# CW308T_ADUCM3029_UFO.net
KiCad netlist of a schematic drawn in Altium Designer
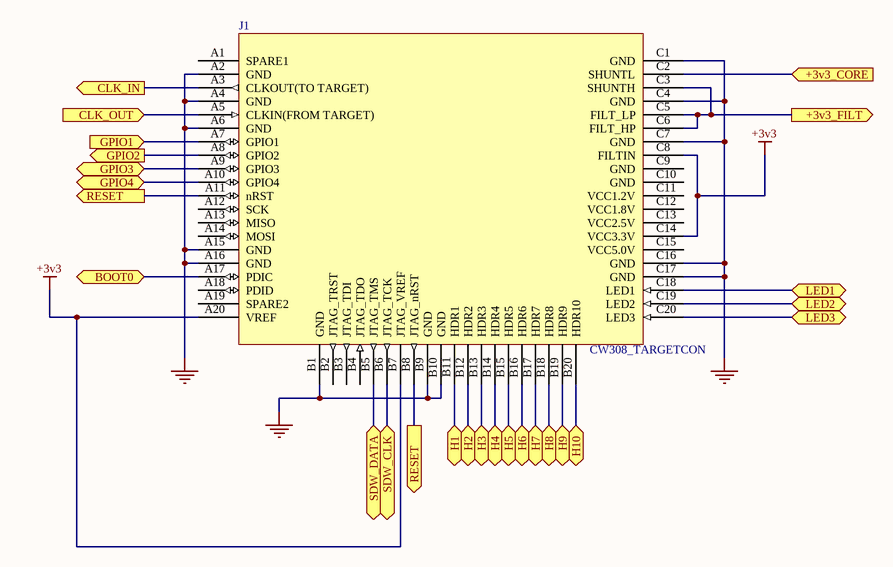
[diagram p0: CW308T_ADUCM3029_UFO.SchDoc]

(export (version "E")
  (design (tool "Eeschema 10.0.6"))
  (components
    (comp (ref "J1")
      (value "CW308_TARGETCON")
      (footprint "CW308_TBOARD_CONN")
      (description "CW308 \"Standard\" Target Board Connector")
      (fields (field (name "PART NUMBER") "CW308_TBOARD"))
      (libsource (lib "NewAE_AltiumLib") (part "CW308_TBOARD"))
    )
  )
  (nets
    (net (code "1") (name "+3v3") (class "Default")
      (node (ref "J1") (pin "A20") (pinfunction "VREF_A20") (pintype "tri_state"))
      (node (ref "J1") (pin "B7") (pinfunction "JTAG_VREF_B7") (pintype "tri_state"))
      (node (ref "J1") (pin "C14") (pinfunction "VCC3.3V_C14") (pintype "power_in"))
      (node (ref "J1") (pin "C8") (pinfunction "FILTIN_C8") (pintype "passive"))
    )
    (net (code "2") (name "/+3v3_CORE") (class "Default")
      (node (ref "J1") (pin "C2") (pinfunction "SHUNTL_C2") (pintype "passive"))
    )
    (net (code "3") (name "/+3v3_FILT") (class "Default")
      (node (ref "J1") (pin "C3") (pinfunction "SHUNTH_C3") (pintype "passive"))
      (node (ref "J1") (pin "C5") (pinfunction "FILT_LP_C5") (pintype "passive"))
      (node (ref "J1") (pin "C6") (pinfunction "FILT_HP_C6") (pintype "passive"))
    )
    (net (code "4") (name "/BOOT0") (class "Default")
      (node (ref "J1") (pin "A17") (pinfunction "PDIC_A17") (pintype "bidirectional"))
    )
    (net (code "5") (name "/CLK_IN") (class "Default")
      (node (ref "J1") (pin "A3") (pinfunction "CLKOUT(TO_TARGET)_A3") (pintype "output"))
    )
    (net (code "6") (name "/CLK_OUT") (class "Default")
      (node (ref "J1") (pin "A5") (pinfunction "CLKIN(FROM_TARGET)_A5") (pintype "input"))
    )
    (net (code "7") (name "/GPIO1") (class "Default")
      (node (ref "J1") (pin "A7") (pinfunction "GPIO1_A7") (pintype "bidirectional"))
    )
    (net (code "8") (name "/GPIO2") (class "Default")
      (node (ref "J1") (pin "A8") (pinfunction "GPIO2_A8") (pintype "bidirectional"))
    )
    (net (code "9") (name "/GPIO3") (class "Default")
      (node (ref "J1") (pin "A9") (pinfunction "GPIO3_A9") (pintype "bidirectional"))
    )
    (net (code "10") (name "/GPIO4") (class "Default")
      (node (ref "J1") (pin "A10") (pinfunction "GPIO4_A10") (pintype "bidirectional"))
    )
    (net (code "11") (name "/H1") (class "Default")
      (node (ref "J1") (pin "B11") (pinfunction "HDR1_B11") (pintype "passive"))
    )
    (net (code "12") (name "/H2") (class "Default")
      (node (ref "J1") (pin "B12") (pinfunction "HDR2_B12") (pintype "passive"))
    )
    (net (code "13") (name "/H3") (class "Default")
      (node (ref "J1") (pin "B13") (pinfunction "HDR3_B13") (pintype "passive"))
    )
    (net (code "14") (name "/H4") (class "Default")
      (node (ref "J1") (pin "B14") (pinfunction "HDR4_B14") (pintype "passive"))
    )
    (net (code "15") (name "/H5") (class "Default")
      (node (ref "J1") (pin "B15") (pinfunction "HDR5_B15") (pintype "passive"))
    )
    (net (code "16") (name "/H6") (class "Default")
      (node (ref "J1") (pin "B16") (pinfunction "HDR6_B16") (pintype "passive"))
    )
    (net (code "17") (name "/H7") (class "Default")
      (node (ref "J1") (pin "B17") (pinfunction "HDR7_B17") (pintype "passive"))
    )
    (net (code "18") (name "/H8") (class "Default")
      (node (ref "J1") (pin "B18") (pinfunction "HDR8_B18") (pintype "passive"))
    )
    (net (code "19") (name "/H9") (class "Default")
      (node (ref "J1") (pin "B19") (pinfunction "HDR9_B19") (pintype "passive"))
    )
    (net (code "20") (name "/H10") (class "Default")
      (node (ref "J1") (pin "B20") (pinfunction "HDR10_B20") (pintype "passive"))
    )
    (net (code "21") (name "/LED1") (class "Default")
      (node (ref "J1") (pin "C18") (pinfunction "LED1_C18") (pintype "input"))
    )
    (net (code "22") (name "/LED2") (class "Default")
      (node (ref "J1") (pin "C19") (pinfunction "LED2_C19") (pintype "input"))
    )
    (net (code "23") (name "/LED3") (class "Default")
      (node (ref "J1") (pin "C20") (pinfunction "LED3_C20") (pintype "input"))
    )
    (net (code "24") (name "/RESET") (class "Default")
      (node (ref "J1") (pin "A11") (pinfunction "nRST_A11") (pintype "bidirectional"))
      (node (ref "J1") (pin "B8") (pinfunction "JTAG_nRST_B8") (pintype "output"))
    )
    (net (code "25") (name "/SDW_CLK") (class "Default")
      (node (ref "J1") (pin "B6") (pinfunction "JTAG_TCK_B6") (pintype "output"))
    )
    (net (code "26") (name "/SDW_DATA") (class "Default")
      (node (ref "J1") (pin "B5") (pinfunction "JTAG_TMS_B5") (pintype "output"))
    )
    (net (code "27") (name "GND") (class "Default")
      (node (ref "J1") (pin "A15") (pinfunction "GND_A15") (pintype "passive"))
      (node (ref "J1") (pin "A16") (pinfunction "GND_A16") (pintype "passive"))
      (node (ref "J1") (pin "A2") (pinfunction "GND_A2") (pintype "passive"))
      (node (ref "J1") (pin "A4") (pinfunction "GND_A4") (pintype "passive"))
      (node (ref "J1") (pin "A6") (pinfunction "GND_A6") (pintype "power_in"))
      (node (ref "J1") (pin "B1") (pinfunction "GND_B1") (pintype "passive"))
      (node (ref "J1") (pin "B10") (pinfunction "GND_B10") (pintype "passive"))
      (node (ref "J1") (pin "B9") (pinfunction "GND_B9") (pintype "passive"))
      (node (ref "J1") (pin "C1") (pinfunction "GND_C1") (pintype "power_in"))
      (node (ref "J1") (pin "C16") (pinfunction "GND_C16") (pintype "power_in"))
      (node (ref "J1") (pin "C17") (pinfunction "GND_C17") (pintype "power_in"))
      (node (ref "J1") (pin "C4") (pinfunction "GND_C4") (pintype "power_in"))
      (node (ref "J1") (pin "C7") (pinfunction "GND_C7") (pintype "power_in"))
    )
    (net (code "28") (name "unconnected-(J1-GND-PadC9)") (class "Default")
      (node (ref "J1") (pin "C9") (pinfunction "GND_C9") (pintype "power_in"))
    )
    (net (code "29") (name "unconnected-(J1-GND-PadC10)") (class "Default")
      (node (ref "J1") (pin "C10") (pinfunction "GND_C10") (pintype "power_in"))
    )
    (net (code "30") (name "unconnected-(J1-JTAG_TDI-PadB3)") (class "Default")
      (node (ref "J1") (pin "B3") (pinfunction "JTAG_TDI_B3") (pintype "output"))
    )
    (net (code "31") (name "unconnected-(J1-JTAG_TDO-PadB4)") (class "Default")
      (node (ref "J1") (pin "B4") (pinfunction "JTAG_TDO_B4") (pintype "input"))
    )
    (net (code "32") (name "unconnected-(J1-JTAG_TRST-PadB2)") (class "Default")
      (node (ref "J1") (pin "B2") (pinfunction "JTAG_TRST_B2") (pintype "output"))
    )
    (net (code "33") (name "unconnected-(J1-MISO-PadA13)") (class "Default")
      (node (ref "J1") (pin "A13") (pinfunction "MISO_A13") (pintype "bidirectional"))
    )
    (net (code "34") (name "unconnected-(J1-MOSI-PadA14)") (class "Default")
      (node (ref "J1") (pin "A14") (pinfunction "MOSI_A14") (pintype "bidirectional"))
    )
    (net (code "35") (name "unconnected-(J1-PDID-PadA18)") (class "Default")
      (node (ref "J1") (pin "A18") (pinfunction "PDID_A18") (pintype "bidirectional"))
    )
    (net (code "36") (name "unconnected-(J1-SCK-PadA12)") (class "Default")
      (node (ref "J1") (pin "A12") (pinfunction "SCK_A12") (pintype "bidirectional"))
    )
    (net (code "37") (name "unconnected-(J1-SPARE1-PadA1)") (class "Default")
      (node (ref "J1") (pin "A1") (pinfunction "SPARE1_A1") (pintype "passive"))
    )
    (net (code "38") (name "unconnected-(J1-SPARE2-PadA19)") (class "Default")
      (node (ref "J1") (pin "A19") (pinfunction "SPARE2_A19") (pintype "passive"))
    )
    (net (code "39") (name "unconnected-(J1-VCC1.2V-PadC11)") (class "Default")
      (node (ref "J1") (pin "C11") (pinfunction "VCC1.2V_C11") (pintype "power_in"))
    )
    (net (code "40") (name "unconnected-(J1-VCC1.8V-PadC12)") (class "Default")
      (node (ref "J1") (pin "C12") (pinfunction "VCC1.8V_C12") (pintype "power_in"))
    )
    (net (code "41") (name "unconnected-(J1-VCC2.5V-PadC13)") (class "Default")
      (node (ref "J1") (pin "C13") (pinfunction "VCC2.5V_C13") (pintype "power_in"))
    )
    (net (code "42") (name "unconnected-(J1-VCC5.0V-PadC15)") (class "Default")
      (node (ref "J1") (pin "C15") (pinfunction "VCC5.0V_C15") (pintype "power_in"))
    )
  )
)
